# Low_Side_Drivers.net
KiCad netlist of a schematic drawn in Altium Designer
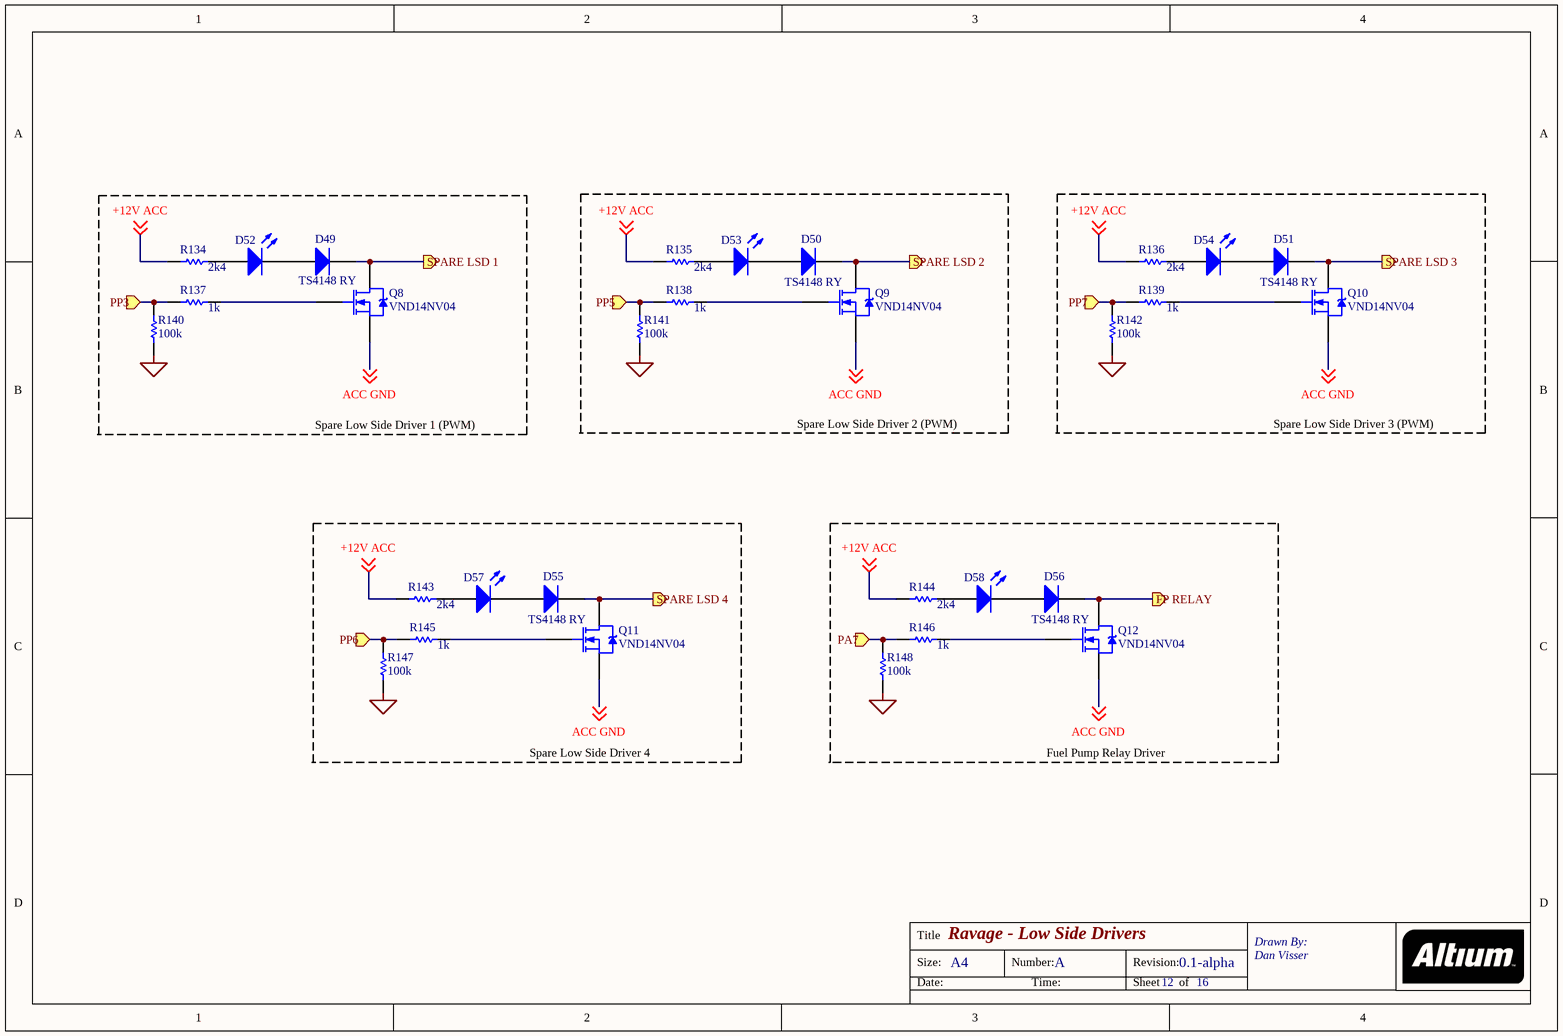
[diagram p0: Low Side Drivers.SchDoc]

(export (version "E")
  (design (tool "Eeschema 10.0.6"))
  (components
    (comp (ref "D49")
      (value "TS4148 RY")
      (footprint "SMC")
      (description "Default Diode")
      (fields (field (name "PUBLISHER") "Altium Limited"))
      (libsource (lib "Miscellaneous Devices") (part "Diode"))
    )
    (comp (ref "D50")
      (value "TS4148 RY")
      (footprint "SMC")
      (description "Default Diode")
      (fields (field (name "PUBLISHER") "Altium Limited"))
      (libsource (lib "Miscellaneous Devices") (part "Diode"))
    )
    (comp (ref "D51")
      (value "TS4148 RY")
      (footprint "SMC")
      (description "Default Diode")
      (fields (field (name "PUBLISHER") "Altium Limited"))
      (libsource (lib "Miscellaneous Devices") (part "Diode"))
    )
    (comp (ref "D52")
      (value "~")
      (footprint "LED-0")
      (description "Typical INFRARED GaAs LED")
      (fields (field (name "PUBLISHER") "Altium Limited"))
      (libsource (lib "Miscellaneous Devices") (part "LED0"))
    )
    (comp (ref "D53")
      (value "~")
      (footprint "LED-0")
      (description "Typical INFRARED GaAs LED")
      (fields (field (name "PUBLISHER") "Altium Limited"))
      (libsource (lib "Miscellaneous Devices") (part "LED0"))
    )
    (comp (ref "D54")
      (value "~")
      (footprint "LED-0")
      (description "Typical INFRARED GaAs LED")
      (fields (field (name "PUBLISHER") "Altium Limited"))
      (libsource (lib "Miscellaneous Devices") (part "LED0"))
    )
    (comp (ref "D55")
      (value "TS4148 RY")
      (footprint "SMC")
      (description "Default Diode")
      (fields (field (name "PUBLISHER") "Altium Limited"))
      (libsource (lib "Miscellaneous Devices") (part "Diode"))
    )
    (comp (ref "D56")
      (value "TS4148 RY")
      (footprint "SMC")
      (description "Default Diode")
      (fields (field (name "PUBLISHER") "Altium Limited"))
      (libsource (lib "Miscellaneous Devices") (part "Diode"))
    )
    (comp (ref "D57")
      (value "~")
      (footprint "LED-0")
      (description "Typical INFRARED GaAs LED")
      (fields (field (name "PUBLISHER") "Altium Limited"))
      (libsource (lib "Miscellaneous Devices") (part "LED0"))
    )
    (comp (ref "D58")
      (value "~")
      (footprint "LED-0")
      (description "Typical INFRARED GaAs LED")
      (fields (field (name "PUBLISHER") "Altium Limited"))
      (libsource (lib "Miscellaneous Devices") (part "LED0"))
    )
    (comp (ref "Q8")
      (value "VND14NV04")
      (footprint "TO-220AB")
      (description "HEXFET Power MOSFET")
      (fields (field (name "PUBLISHER") "Altium Limited"))
      (libsource (lib "IR Discrete MOSFET - Power") (part "IRL520N"))
    )
    (comp (ref "Q9")
      (value "VND14NV04")
      (footprint "TO-220AB")
      (description "HEXFET Power MOSFET")
      (fields (field (name "PUBLISHER") "Altium Limited"))
      (libsource (lib "IR Discrete MOSFET - Power") (part "IRL520N"))
    )
    (comp (ref "Q10")
      (value "VND14NV04")
      (footprint "TO-220AB")
      (description "HEXFET Power MOSFET")
      (fields (field (name "PUBLISHER") "Altium Limited"))
      (libsource (lib "IR Discrete MOSFET - Power") (part "IRL520N"))
    )
    (comp (ref "Q11")
      (value "VND14NV04")
      (footprint "TO-220AB")
      (description "HEXFET Power MOSFET")
      (fields (field (name "PUBLISHER") "Altium Limited"))
      (libsource (lib "IR Discrete MOSFET - Power") (part "IRL520N"))
    )
    (comp (ref "Q12")
      (value "VND14NV04")
      (footprint "TO-220AB")
      (description "HEXFET Power MOSFET")
      (fields (field (name "PUBLISHER") "Altium Limited"))
      (libsource (lib "IR Discrete MOSFET - Power") (part "IRL520N"))
    )
    (comp (ref "R134")
      (value "2k4")
      (footprint "AXIAL-0.3")
      (description "Resistor")
      (fields (field (name "PUBLISHER") "Altium Limited"))
      (libsource (lib "Miscellaneous Devices") (part "Res1"))
    )
    (comp (ref "R135")
      (value "2k4")
      (footprint "AXIAL-0.3")
      (description "Resistor")
      (fields (field (name "PUBLISHER") "Altium Limited"))
      (libsource (lib "Miscellaneous Devices") (part "Res1"))
    )
    (comp (ref "R136")
      (value "2k4")
      (footprint "AXIAL-0.3")
      (description "Resistor")
      (fields (field (name "PUBLISHER") "Altium Limited"))
      (libsource (lib "Miscellaneous Devices") (part "Res1"))
    )
    (comp (ref "R137")
      (value "1k")
      (footprint "AXIAL-0.3")
      (description "Resistor")
      (fields (field (name "PUBLISHER") "Altium Limited"))
      (libsource (lib "Miscellaneous Devices") (part "Res1"))
    )
    (comp (ref "R138")
      (value "1k")
      (footprint "AXIAL-0.3")
      (description "Resistor")
      (fields (field (name "PUBLISHER") "Altium Limited"))
      (libsource (lib "Miscellaneous Devices") (part "Res1"))
    )
    (comp (ref "R139")
      (value "1k")
      (footprint "AXIAL-0.3")
      (description "Resistor")
      (fields (field (name "PUBLISHER") "Altium Limited"))
      (libsource (lib "Miscellaneous Devices") (part "Res1"))
    )
    (comp (ref "R140")
      (value "100k")
      (footprint "AXIAL-0.3")
      (description "Resistor")
      (fields (field (name "PUBLISHER") "Altium Limited"))
      (libsource (lib "Miscellaneous Devices") (part "Res1"))
    )
    (comp (ref "R141")
      (value "100k")
      (footprint "AXIAL-0.3")
      (description "Resistor")
      (fields (field (name "PUBLISHER") "Altium Limited"))
      (libsource (lib "Miscellaneous Devices") (part "Res1"))
    )
    (comp (ref "R142")
      (value "100k")
      (footprint "AXIAL-0.3")
      (description "Resistor")
      (fields (field (name "PUBLISHER") "Altium Limited"))
      (libsource (lib "Miscellaneous Devices") (part "Res1"))
    )
    (comp (ref "R143")
      (value "2k4")
      (footprint "AXIAL-0.3")
      (description "Resistor")
      (fields (field (name "PUBLISHER") "Altium Limited"))
      (libsource (lib "Miscellaneous Devices") (part "Res1"))
    )
    (comp (ref "R144")
      (value "2k4")
      (footprint "AXIAL-0.3")
      (description "Resistor")
      (fields (field (name "PUBLISHER") "Altium Limited"))
      (libsource (lib "Miscellaneous Devices") (part "Res1"))
    )
    (comp (ref "R145")
      (value "1k")
      (footprint "AXIAL-0.3")
      (description "Resistor")
      (fields (field (name "PUBLISHER") "Altium Limited"))
      (libsource (lib "Miscellaneous Devices") (part "Res1"))
    )
    (comp (ref "R146")
      (value "1k")
      (footprint "AXIAL-0.3")
      (description "Resistor")
      (fields (field (name "PUBLISHER") "Altium Limited"))
      (libsource (lib "Miscellaneous Devices") (part "Res1"))
    )
    (comp (ref "R147")
      (value "100k")
      (footprint "AXIAL-0.3")
      (description "Resistor")
      (fields (field (name "PUBLISHER") "Altium Limited"))
      (libsource (lib "Miscellaneous Devices") (part "Res1"))
    )
    (comp (ref "R148")
      (value "100k")
      (footprint "AXIAL-0.3")
      (description "Resistor")
      (fields (field (name "PUBLISHER") "Altium Limited"))
      (libsource (lib "Miscellaneous Devices") (part "Res1"))
    )
  )
  (nets
    (net (code "1") (name "+12V ACC") (class "Default")
      (node (ref "R134") (pin "1") (pinfunction "1_1") (pintype "passive"))
      (node (ref "R135") (pin "1") (pinfunction "1_1") (pintype "passive"))
      (node (ref "R136") (pin "1") (pinfunction "1_1") (pintype "passive"))
      (node (ref "R143") (pin "1") (pinfunction "1_1") (pintype "passive"))
      (node (ref "R144") (pin "1") (pinfunction "1_1") (pintype "passive"))
    )
    (net (code "2") (name "/FP RELAY") (class "Default")
      (node (ref "D56") (pin "2") (pinfunction "K_2") (pintype "passive"))
      (node (ref "Q12") (pin "2") (pinfunction "D_2") (pintype "passive"))
    )
    (net (code "3") (name "/PA7") (class "Default")
      (node (ref "R146") (pin "1") (pinfunction "1_1") (pintype "passive"))
      (node (ref "R148") (pin "2") (pinfunction "2_2") (pintype "passive"))
    )
    (net (code "4") (name "/PP3") (class "Default")
      (node (ref "R137") (pin "1") (pinfunction "1_1") (pintype "passive"))
      (node (ref "R140") (pin "2") (pinfunction "2_2") (pintype "passive"))
    )
    (net (code "5") (name "/PP5") (class "Default")
      (node (ref "R138") (pin "1") (pinfunction "1_1") (pintype "passive"))
      (node (ref "R141") (pin "2") (pinfunction "2_2") (pintype "passive"))
    )
    (net (code "6") (name "/PP6") (class "Default")
      (node (ref "R145") (pin "1") (pinfunction "1_1") (pintype "passive"))
      (node (ref "R147") (pin "2") (pinfunction "2_2") (pintype "passive"))
    )
    (net (code "7") (name "/PP7") (class "Default")
      (node (ref "R139") (pin "1") (pinfunction "1_1") (pintype "passive"))
      (node (ref "R142") (pin "2") (pinfunction "2_2") (pintype "passive"))
    )
    (net (code "8") (name "/SPARE LSD 1") (class "Default")
      (node (ref "D49") (pin "2") (pinfunction "K_2") (pintype "passive"))
      (node (ref "Q8") (pin "2") (pinfunction "D_2") (pintype "passive"))
    )
    (net (code "9") (name "/SPARE LSD 2") (class "Default")
      (node (ref "D50") (pin "2") (pinfunction "K_2") (pintype "passive"))
      (node (ref "Q9") (pin "2") (pinfunction "D_2") (pintype "passive"))
    )
    (net (code "10") (name "/SPARE LSD 3") (class "Default")
      (node (ref "D51") (pin "2") (pinfunction "K_2") (pintype "passive"))
      (node (ref "Q10") (pin "2") (pinfunction "D_2") (pintype "passive"))
    )
    (net (code "11") (name "/SPARE LSD 4") (class "Default")
      (node (ref "D55") (pin "2") (pinfunction "K_2") (pintype "passive"))
      (node (ref "Q11") (pin "2") (pinfunction "D_2") (pintype "passive"))
    )
    (net (code "12") (name "<NO NET>") (class "Default")
      (node (ref "R140") (pin "1") (pinfunction "1_1") (pintype "passive"))
      (node (ref "R141") (pin "1") (pinfunction "1_1") (pintype "passive"))
      (node (ref "R142") (pin "1") (pinfunction "1_1") (pintype "passive"))
      (node (ref "R147") (pin "1") (pinfunction "1_1") (pintype "passive"))
      (node (ref "R148") (pin "1") (pinfunction "1_1") (pintype "passive"))
    )
    (net (code "13") (name "ACC GND") (class "Default")
      (node (ref "Q10") (pin "3") (pinfunction "S_3") (pintype "passive"))
      (node (ref "Q11") (pin "3") (pinfunction "S_3") (pintype "passive"))
      (node (ref "Q12") (pin "3") (pinfunction "S_3") (pintype "passive"))
      (node (ref "Q8") (pin "3") (pinfunction "S_3") (pintype "passive"))
      (node (ref "Q9") (pin "3") (pinfunction "S_3") (pintype "passive"))
    )
    (net (code "14") (name "Net-(D49-A)") (class "Default")
      (node (ref "D49") (pin "1") (pinfunction "A_1") (pintype "passive"))
      (node (ref "D52") (pin "2") (pinfunction "K_2") (pintype "passive"))
    )
    (net (code "15") (name "Net-(D50-A)") (class "Default")
      (node (ref "D50") (pin "1") (pinfunction "A_1") (pintype "passive"))
      (node (ref "D53") (pin "2") (pinfunction "K_2") (pintype "passive"))
    )
    (net (code "16") (name "Net-(D51-A)") (class "Default")
      (node (ref "D51") (pin "1") (pinfunction "A_1") (pintype "passive"))
      (node (ref "D54") (pin "2") (pinfunction "K_2") (pintype "passive"))
    )
    (net (code "17") (name "Net-(D52-A)") (class "Default")
      (node (ref "D52") (pin "1") (pinfunction "A_1") (pintype "passive"))
      (node (ref "R134") (pin "2") (pinfunction "2_2") (pintype "passive"))
    )
    (net (code "18") (name "Net-(D53-A)") (class "Default")
      (node (ref "D53") (pin "1") (pinfunction "A_1") (pintype "passive"))
      (node (ref "R135") (pin "2") (pinfunction "2_2") (pintype "passive"))
    )
    (net (code "19") (name "Net-(D54-A)") (class "Default")
      (node (ref "D54") (pin "1") (pinfunction "A_1") (pintype "passive"))
      (node (ref "R136") (pin "2") (pinfunction "2_2") (pintype "passive"))
    )
    (net (code "20") (name "Net-(D55-A)") (class "Default")
      (node (ref "D55") (pin "1") (pinfunction "A_1") (pintype "passive"))
      (node (ref "D57") (pin "2") (pinfunction "K_2") (pintype "passive"))
    )
    (net (code "21") (name "Net-(D56-A)") (class "Default")
      (node (ref "D56") (pin "1") (pinfunction "A_1") (pintype "passive"))
      (node (ref "D58") (pin "2") (pinfunction "K_2") (pintype "passive"))
    )
    (net (code "22") (name "Net-(D57-A)") (class "Default")
      (node (ref "D57") (pin "1") (pinfunction "A_1") (pintype "passive"))
      (node (ref "R143") (pin "2") (pinfunction "2_2") (pintype "passive"))
    )
    (net (code "23") (name "Net-(D58-A)") (class "Default")
      (node (ref "D58") (pin "1") (pinfunction "A_1") (pintype "passive"))
      (node (ref "R144") (pin "2") (pinfunction "2_2") (pintype "passive"))
    )
    (net (code "24") (name "Net-(Q8-G)") (class "Default")
      (node (ref "Q8") (pin "1") (pinfunction "G_1") (pintype "passive"))
      (node (ref "R137") (pin "2") (pinfunction "2_2") (pintype "passive"))
    )
    (net (code "25") (name "Net-(Q9-G)") (class "Default")
      (node (ref "Q9") (pin "1") (pinfunction "G_1") (pintype "passive"))
      (node (ref "R138") (pin "2") (pinfunction "2_2") (pintype "passive"))
    )
    (net (code "26") (name "Net-(Q10-G)") (class "Default")
      (node (ref "Q10") (pin "1") (pinfunction "G_1") (pintype "passive"))
      (node (ref "R139") (pin "2") (pinfunction "2_2") (pintype "passive"))
    )
    (net (code "27") (name "Net-(Q11-G)") (class "Default")
      (node (ref "Q11") (pin "1") (pinfunction "G_1") (pintype "passive"))
      (node (ref "R145") (pin "2") (pinfunction "2_2") (pintype "passive"))
    )
    (net (code "28") (name "Net-(Q12-G)") (class "Default")
      (node (ref "Q12") (pin "1") (pinfunction "G_1") (pintype "passive"))
      (node (ref "R146") (pin "2") (pinfunction "2_2") (pintype "passive"))
    )
  )
)
